# A3977_single_axis.net
KiCad netlist of a schematic drawn in EAGLE
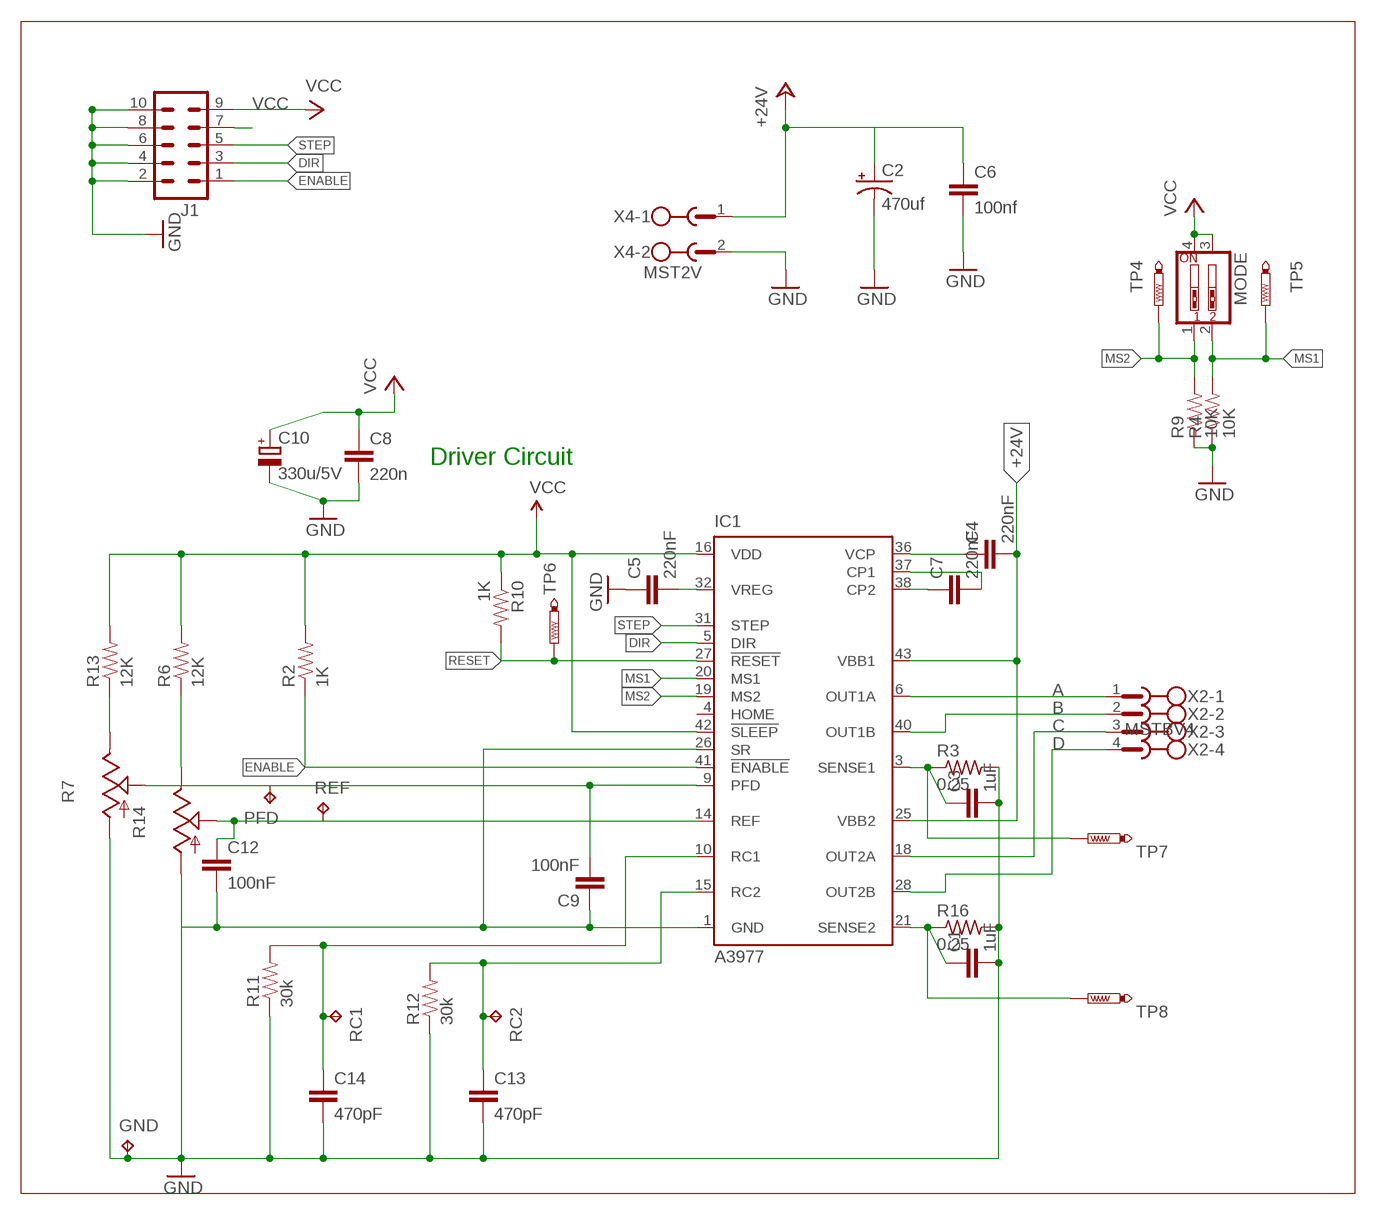
[diagram p0: schematic, sheet 1]

(export (version "E")
  (design (tool "Eeschema 10.0.6"))
  (components
    (comp (ref "C1")
      (value "1uF")
      (footprint "eagle-import:0805")
      (libsource (lib "eagle-import") (part "CAP0805"))
    )
    (comp (ref "C2")
      (value "470uf")
      (footprint "eagle-import:NIC_10X10.5_CAP")
      (libsource (lib "eagle-import") (part "100UF-63V-20%(ELECT)"))
    )
    (comp (ref "C3")
      (value "1uF")
      (footprint "eagle-import:0805")
      (libsource (lib "eagle-import") (part "CAP0805"))
    )
    (comp (ref "C4")
      (value "220nF")
      (footprint "eagle-import:0805")
      (libsource (lib "eagle-import") (part "CAP0805"))
    )
    (comp (ref "C5")
      (value "220nF")
      (footprint "eagle-import:0805")
      (libsource (lib "eagle-import") (part "CAP0805"))
    )
    (comp (ref "C6")
      (value "100nf")
      (footprint "eagle-import:C1206")
      (libsource (lib "eagle-import") (part "resistor_C-EUC1206"))
    )
    (comp (ref "C7")
      (value "220nF")
      (footprint "eagle-import:0805")
      (libsource (lib "eagle-import") (part "CAP0805"))
    )
    (comp (ref "C8")
      (value "220n")
      (footprint "eagle-import:C0805")
      (libsource (lib "eagle-import") (part "C-EUC0805"))
    )
    (comp (ref "C9")
      (value "100nF")
      (footprint "eagle-import:0805")
      (libsource (lib "eagle-import") (part "CAP0805"))
    )
    (comp (ref "C10")
      (value "330u/5V")
      (footprint "eagle-import:PANASONIC_F")
      (libsource (lib "eagle-import") (part "CPOL-EUF"))
    )
    (comp (ref "C12")
      (value "100nF")
      (footprint "eagle-import:0805")
      (libsource (lib "eagle-import") (part "CAP0805"))
    )
    (comp (ref "C13")
      (value "470pF")
      (footprint "eagle-import:0805")
      (libsource (lib "eagle-import") (part "CAP0805"))
    )
    (comp (ref "C14")
      (value "470pF")
      (footprint "eagle-import:0805")
      (libsource (lib "eagle-import") (part "CAP0805"))
    )
    (comp (ref "GND")
      (value "TPPAD1-13")
      (footprint "eagle-import:P1-13")
      (libsource (lib "eagle-import") (part "TPPAD1-13"))
    )
    (comp (ref "IC1")
      (value "A3977")
      (footprint "eagle-import:PLCC44")
      (libsource (lib "eagle-import") (part "A3977"))
    )
    (comp (ref "J1")
      (value "M05X2SHD")
      (footprint "eagle-import:2X5-SHROUDED")
      (libsource (lib "eagle-import") (part "M05X2SHD"))
    )
    (comp (ref "MODE")
      (value "SW_DIP-2")
      (footprint "eagle-import:EDG-02")
      (libsource (lib "eagle-import") (part "SW_DIP-2"))
    )
    (comp (ref "PFD")
      (value "TPPAD1-13")
      (footprint "eagle-import:P1-13")
      (libsource (lib "eagle-import") (part "TPPAD1-13"))
    )
    (comp (ref "R2")
      (value "1K")
      (footprint "eagle-import:0805")
      (libsource (lib "eagle-import") (part "RESISTOR"))
    )
    (comp (ref "R3")
      (value "0.25")
      (footprint "eagle-import:R2512")
      (libsource (lib "eagle-import") (part "R-US_R2512"))
    )
    (comp (ref "R4")
      (value "10K")
      (footprint "eagle-import:0805")
      (libsource (lib "eagle-import") (part "RESISTOR"))
    )
    (comp (ref "R6")
      (value "12K")
      (footprint "eagle-import:0805")
      (libsource (lib "eagle-import") (part "RESISTOR"))
    )
    (comp (ref "R7")
      (value "TRIM_US-CA6V")
      (footprint "eagle-import:CA6V")
      (libsource (lib "eagle-import") (part "TRIM_US-CA6V"))
    )
    (comp (ref "R9")
      (value "10K")
      (footprint "eagle-import:0805")
      (libsource (lib "eagle-import") (part "RESISTOR"))
    )
    (comp (ref "R10")
      (value "1K")
      (footprint "eagle-import:0805")
      (libsource (lib "eagle-import") (part "RESISTOR"))
    )
    (comp (ref "R11")
      (value "30k")
      (footprint "eagle-import:0805")
      (libsource (lib "eagle-import") (part "RESISTOR"))
    )
    (comp (ref "R12")
      (value "30k")
      (footprint "eagle-import:0805")
      (libsource (lib "eagle-import") (part "RESISTOR"))
    )
    (comp (ref "R13")
      (value "12K")
      (footprint "eagle-import:0805")
      (libsource (lib "eagle-import") (part "RESISTOR"))
    )
    (comp (ref "R14")
      (value "TRIM_US-CA6V")
      (footprint "eagle-import:CA6V")
      (libsource (lib "eagle-import") (part "TRIM_US-CA6V"))
    )
    (comp (ref "R16")
      (value "0.25")
      (footprint "eagle-import:R2512")
      (libsource (lib "eagle-import") (part "R-US_R2512"))
    )
    (comp (ref "RC1")
      (value "TPPAD1-13")
      (footprint "eagle-import:P1-13")
      (libsource (lib "eagle-import") (part "TPPAD1-13"))
    )
    (comp (ref "RC2")
      (value "TPPAD1-13")
      (footprint "eagle-import:P1-13")
      (libsource (lib "eagle-import") (part "TPPAD1-13"))
    )
    (comp (ref "REF")
      (value "TPPAD1-13")
      (footprint "eagle-import:P1-13")
      (libsource (lib "eagle-import") (part "TPPAD1-13"))
    )
    (comp (ref "TP4")
      (value "PTR1TP09R")
      (footprint "eagle-import:TP09R")
      (libsource (lib "eagle-import") (part "PTR1TP09R"))
    )
    (comp (ref "TP5")
      (value "PTR1TP09R")
      (footprint "eagle-import:TP09R")
      (libsource (lib "eagle-import") (part "PTR1TP09R"))
    )
    (comp (ref "TP6")
      (value "PTR1TP09R")
      (footprint "eagle-import:TP09R")
      (libsource (lib "eagle-import") (part "PTR1TP09R"))
    )
    (comp (ref "TP7")
      (value "PTR1TP09R")
      (footprint "eagle-import:TP09R")
      (libsource (lib "eagle-import") (part "PTR1TP09R"))
    )
    (comp (ref "TP8")
      (value "PTR1TP09R")
      (footprint "eagle-import:TP09R")
      (libsource (lib "eagle-import") (part "PTR1TP09R"))
    )
    (comp (ref "X2")
      (value "MSTBV4")
      (footprint "eagle-import:MSTBV4")
      (fields (field (name "MPN") "MSTBV 2,5/4-GF-5.08"))
      (libsource (lib "eagle-import") (part "MSTBV4"))
    )
    (comp (ref "X4")
      (value "MST2V")
      (footprint "eagle-import:MSTBV2")
      (libsource (lib "eagle-import") (part "MST2V"))
    )
  )
  (nets
    (net (code "1") (name "+24V") (class "Default")
      (node (ref "C2") (pin "+") (pinfunction "+_+") (pintype "passive"))
      (node (ref "C4") (pin "2") (pinfunction "2_2") (pintype "passive"))
      (node (ref "C6") (pin "1") (pinfunction "1_1") (pintype "passive"))
      (node (ref "IC1") (pin "25") (pinfunction "VBB2_25") (pintype "power_in"))
      (node (ref "IC1") (pin "43") (pinfunction "VBB1_43") (pintype "power_in"))
      (node (ref "X4") (pin "1") (pinfunction "1_1") (pintype "passive"))
    )
    (net (code "2") (name "/A") (class "Default")
      (node (ref "IC1") (pin "6") (pinfunction "OUT1A_6") (pintype "output"))
      (node (ref "X2") (pin "1") (pinfunction "1_1") (pintype "passive"))
    )
    (net (code "3") (name "/B") (class "Default")
      (node (ref "IC1") (pin "40") (pinfunction "OUT1B_40") (pintype "output"))
      (node (ref "X2") (pin "2") (pinfunction "1_2") (pintype "passive"))
    )
    (net (code "4") (name "/C") (class "Default")
      (node (ref "IC1") (pin "18") (pinfunction "OUT2A_18") (pintype "output"))
      (node (ref "X2") (pin "3") (pinfunction "1_3") (pintype "passive"))
    )
    (net (code "5") (name "/D") (class "Default")
      (node (ref "IC1") (pin "28") (pinfunction "OUT2B_28") (pintype "output"))
      (node (ref "X2") (pin "4") (pinfunction "1_4") (pintype "passive"))
    )
    (net (code "6") (name "DIR") (class "Default")
      (node (ref "IC1") (pin "5") (pinfunction "DIR_5") (pintype "input"))
      (node (ref "J1") (pin "3") (pinfunction "3_3") (pintype "passive"))
    )
    (net (code "7") (name "ENABLE") (class "Default")
      (node (ref "IC1") (pin "41") (pinfunction "~{ENABLE}_41") (pintype "input"))
      (node (ref "J1") (pin "1") (pinfunction "1_1") (pintype "passive"))
      (node (ref "R2") (pin "1") (pinfunction "1_1") (pintype "passive"))
    )
    (net (code "8") (name "GND") (class "Default")
      (node (ref "C1") (pin "2") (pinfunction "2_2") (pintype "passive"))
      (node (ref "C10") (pin "-") (pinfunction "-_-") (pintype "passive"))
      (node (ref "C12") (pin "2") (pinfunction "2_2") (pintype "passive"))
      (node (ref "C13") (pin "2") (pinfunction "2_2") (pintype "passive"))
      (node (ref "C14") (pin "2") (pinfunction "2_2") (pintype "passive"))
      (node (ref "C2") (pin "-") (pinfunction "-_-") (pintype "passive"))
      (node (ref "C3") (pin "2") (pinfunction "2_2") (pintype "passive"))
      (node (ref "C5") (pin "1") (pinfunction "1_1") (pintype "passive"))
      (node (ref "C6") (pin "2") (pinfunction "2_2") (pintype "passive"))
      (node (ref "C8") (pin "2") (pinfunction "2_2") (pintype "passive"))
      (node (ref "C9") (pin "1") (pinfunction "1_1") (pintype "passive"))
      (node (ref "GND") (pin "TP") (pinfunction "TP_TP") (pintype "input"))
      (node (ref "IC1") (pin "1") (pinfunction "GND_1") (pintype "power_in"))
      (node (ref "IC1") (pin "26") (pinfunction "SR_26") (pintype "input"))
      (node (ref "J1") (pin "10") (pinfunction "10_10") (pintype "passive"))
      (node (ref "J1") (pin "2") (pinfunction "2_2") (pintype "passive"))
      (node (ref "J1") (pin "4") (pinfunction "4_4") (pintype "passive"))
      (node (ref "J1") (pin "6") (pinfunction "6_6") (pintype "passive"))
      (node (ref "J1") (pin "8") (pinfunction "8_8") (pintype "passive"))
      (node (ref "R11") (pin "1") (pinfunction "1_1") (pintype "passive"))
      (node (ref "R12") (pin "1") (pinfunction "1_1") (pintype "passive"))
      (node (ref "R14") (pin "A") (pinfunction "A_A") (pintype "passive"))
      (node (ref "R16") (pin "2") (pinfunction "2_2") (pintype "passive"))
      (node (ref "R3") (pin "2") (pinfunction "2_2") (pintype "passive"))
      (node (ref "R4") (pin "1") (pinfunction "1_1") (pintype "passive"))
      (node (ref "R7") (pin "A") (pinfunction "A_A") (pintype "passive"))
      (node (ref "R9") (pin "1") (pinfunction "1_1") (pintype "passive"))
      (node (ref "X4") (pin "2") (pinfunction "1_2") (pintype "passive"))
    )
    (net (code "9") (name "MS1") (class "Default")
      (node (ref "IC1") (pin "20") (pinfunction "MS1_20") (pintype "input"))
      (node (ref "MODE") (pin "2") (pinfunction "2_2") (pintype "passive"))
      (node (ref "R4") (pin "2") (pinfunction "2_2") (pintype "passive"))
      (node (ref "TP5") (pin "TP") (pinfunction "TP_TP") (pintype "input"))
    )
    (net (code "10") (name "MS2") (class "Default")
      (node (ref "IC1") (pin "19") (pinfunction "MS2_19") (pintype "input"))
      (node (ref "MODE") (pin "1") (pinfunction "1_1") (pintype "passive"))
      (node (ref "R9") (pin "2") (pinfunction "2_2") (pintype "passive"))
      (node (ref "TP4") (pin "TP") (pinfunction "TP_TP") (pintype "input"))
    )
    (net (code "11") (name "Net-(IC1A-CP1)") (class "Default")
      (node (ref "C7") (pin "2") (pinfunction "2_2") (pintype "passive"))
      (node (ref "IC1") (pin "37") (pinfunction "CP1_37") (pintype "passive"))
    )
    (net (code "12") (name "Net-(IC1A-CP2)") (class "Default")
      (node (ref "C7") (pin "1") (pinfunction "1_1") (pintype "passive"))
      (node (ref "IC1") (pin "38") (pinfunction "CP2_38") (pintype "passive"))
    )
    (net (code "13") (name "Net-(IC1A-PFD)") (class "Default")
      (node (ref "C9") (pin "2") (pinfunction "2_2") (pintype "passive"))
      (node (ref "IC1") (pin "9") (pinfunction "PFD_9") (pintype "input"))
      (node (ref "PFD") (pin "TP") (pinfunction "TP_TP") (pintype "input"))
      (node (ref "R7") (pin "S") (pinfunction "S_S") (pintype "passive"))
    )
    (net (code "14") (name "Net-(IC1A-RC1)") (class "Default")
      (node (ref "C14") (pin "1") (pinfunction "1_1") (pintype "passive"))
      (node (ref "IC1") (pin "10") (pinfunction "RC1_10") (pintype "passive"))
      (node (ref "R11") (pin "2") (pinfunction "2_2") (pintype "passive"))
      (node (ref "RC1") (pin "TP") (pinfunction "TP_TP") (pintype "input"))
    )
    (net (code "15") (name "Net-(IC1A-RC2)") (class "Default")
      (node (ref "C13") (pin "1") (pinfunction "1_1") (pintype "passive"))
      (node (ref "IC1") (pin "15") (pinfunction "RC2_15") (pintype "passive"))
      (node (ref "R12") (pin "2") (pinfunction "2_2") (pintype "passive"))
      (node (ref "RC2") (pin "TP") (pinfunction "TP_TP") (pintype "input"))
    )
    (net (code "16") (name "Net-(IC1A-REF)") (class "Default")
      (node (ref "C12") (pin "1") (pinfunction "1_1") (pintype "passive"))
      (node (ref "IC1") (pin "14") (pinfunction "REF_14") (pintype "input"))
      (node (ref "R14") (pin "S") (pinfunction "S_S") (pintype "passive"))
      (node (ref "REF") (pin "TP") (pinfunction "TP_TP") (pintype "input"))
    )
    (net (code "17") (name "Net-(IC1A-SENSE1)") (class "Default")
      (node (ref "C3") (pin "1") (pinfunction "1_1") (pintype "passive"))
      (node (ref "IC1") (pin "3") (pinfunction "SENSE1_3") (pintype "input"))
      (node (ref "R3") (pin "1") (pinfunction "1_1") (pintype "passive"))
      (node (ref "TP7") (pin "TP") (pinfunction "TP_TP") (pintype "input"))
    )
    (net (code "18") (name "Net-(IC1A-SENSE2)") (class "Default")
      (node (ref "C1") (pin "1") (pinfunction "1_1") (pintype "passive"))
      (node (ref "IC1") (pin "21") (pinfunction "SENSE2_21") (pintype "input"))
      (node (ref "R16") (pin "1") (pinfunction "1_1") (pintype "passive"))
      (node (ref "TP8") (pin "TP") (pinfunction "TP_TP") (pintype "input"))
    )
    (net (code "19") (name "Net-(IC1A-VCP)") (class "Default")
      (node (ref "C4") (pin "1") (pinfunction "1_1") (pintype "passive"))
      (node (ref "IC1") (pin "36") (pinfunction "VCP_36") (pintype "passive"))
    )
    (net (code "20") (name "Net-(IC1A-VREG)") (class "Default")
      (node (ref "C5") (pin "2") (pinfunction "2_2") (pintype "passive"))
      (node (ref "IC1") (pin "32") (pinfunction "VREG_32") (pintype "power_in"))
    )
    (net (code "21") (name "Net-(R13-Pad1)") (class "Default")
      (node (ref "R13") (pin "1") (pinfunction "1_1") (pintype "passive"))
      (node (ref "R7") (pin "E") (pinfunction "E_E") (pintype "passive"))
    )
    (net (code "22") (name "Net-(R14-PadE)") (class "Default")
      (node (ref "R14") (pin "E") (pinfunction "E_E") (pintype "passive"))
      (node (ref "R6") (pin "1") (pinfunction "1_1") (pintype "passive"))
    )
    (net (code "23") (name "RESET") (class "Default")
      (node (ref "IC1") (pin "27") (pinfunction "~{RESET}_27") (pintype "input"))
      (node (ref "R10") (pin "2") (pinfunction "2_2") (pintype "passive"))
      (node (ref "TP6") (pin "TP") (pinfunction "TP_TP") (pintype "input"))
    )
    (net (code "24") (name "STEP") (class "Default")
      (node (ref "IC1") (pin "31") (pinfunction "STEP_31") (pintype "input"))
      (node (ref "J1") (pin "5") (pinfunction "5_5") (pintype "passive"))
    )
    (net (code "25") (name "VCC") (class "Default")
      (node (ref "C10") (pin "+") (pinfunction "+_+") (pintype "passive"))
      (node (ref "C8") (pin "1") (pinfunction "1_1") (pintype "passive"))
      (node (ref "IC1") (pin "16") (pinfunction "VDD_16") (pintype "power_in"))
      (node (ref "IC1") (pin "42") (pinfunction "~{SLEEP}_42") (pintype "input"))
      (node (ref "J1") (pin "9") (pinfunction "9_9") (pintype "passive"))
      (node (ref "MODE") (pin "3") (pinfunction "3_3") (pintype "passive"))
      (node (ref "MODE") (pin "4") (pinfunction "4_4") (pintype "passive"))
      (node (ref "R10") (pin "1") (pinfunction "1_1") (pintype "passive"))
      (node (ref "R13") (pin "2") (pinfunction "2_2") (pintype "passive"))
      (node (ref "R2") (pin "2") (pinfunction "2_2") (pintype "passive"))
      (node (ref "R6") (pin "2") (pinfunction "2_2") (pintype "passive"))
    )
    (net (code "26") (name "unconnected-(IC1A-HOME-Pad4)") (class "Default")
      (node (ref "IC1") (pin "4") (pinfunction "HOME_4") (pintype "input"))
    )
    (net (code "27") (name "unconnected-(J1-Pad7)") (class "Default")
      (node (ref "J1") (pin "7") (pinfunction "7_7") (pintype "passive"))
    )
  )
)
